# PIPTIK.net
KiCad netlist of a schematic drawn in Altium Designer
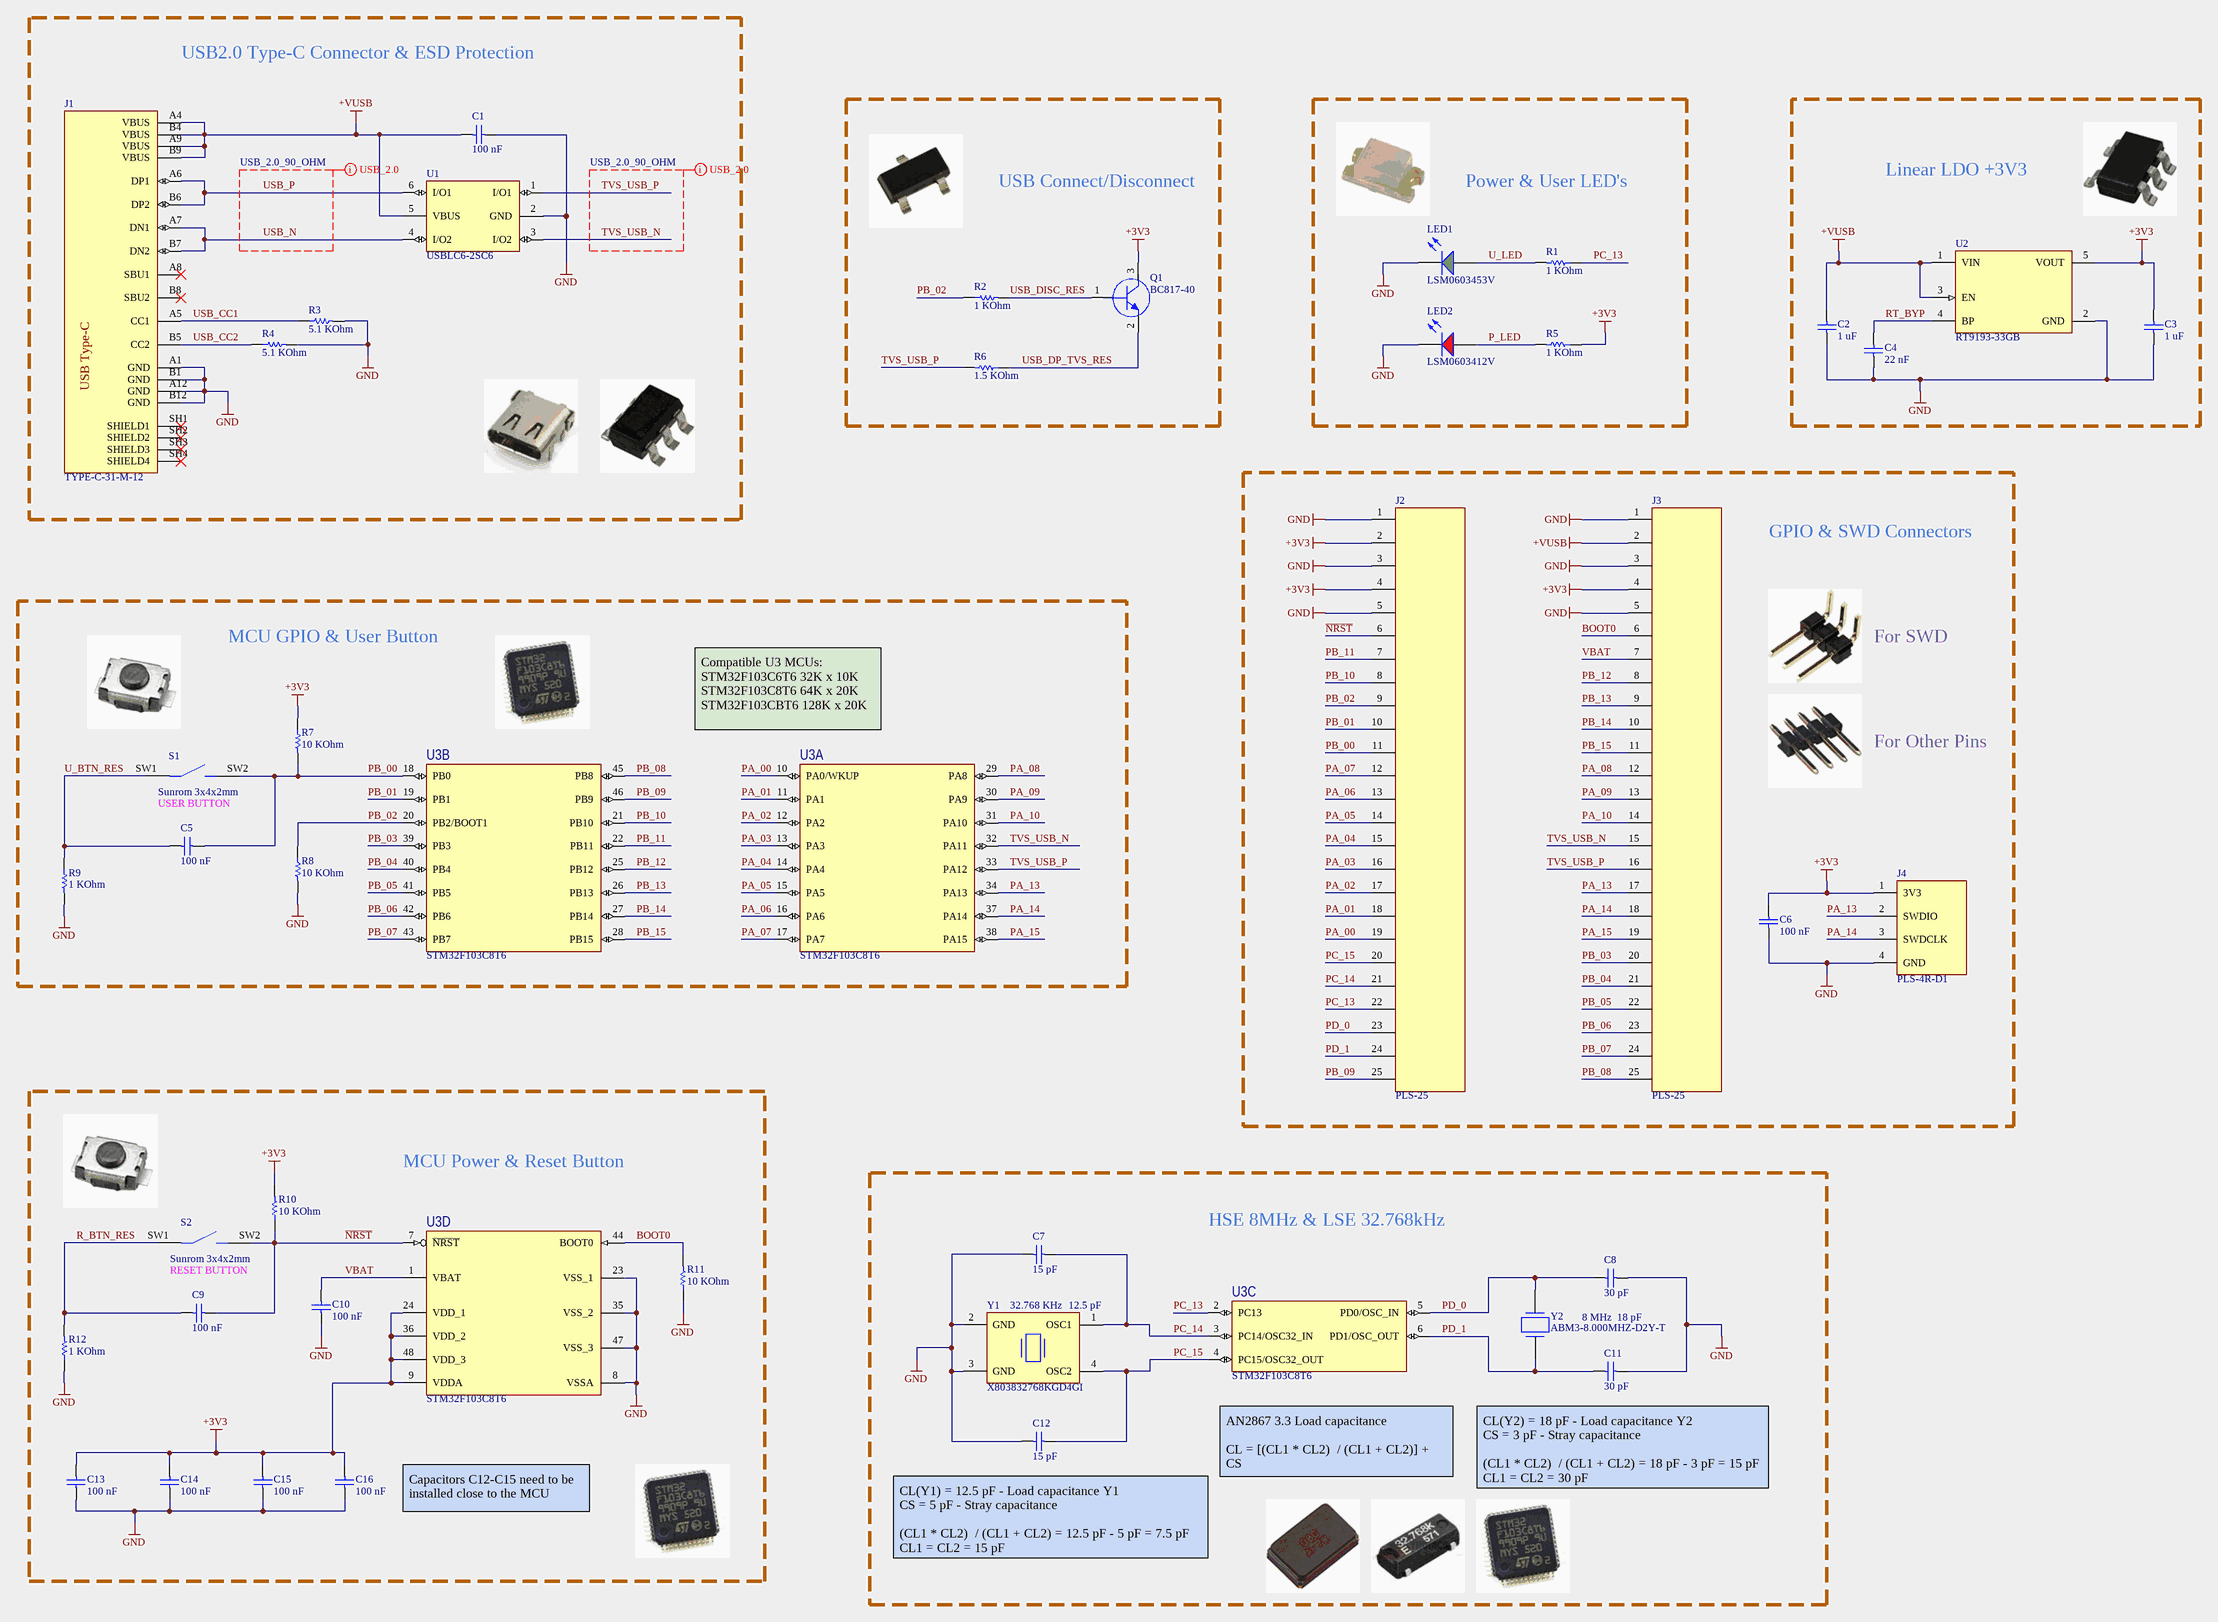
[diagram p0: PIPTIK.SchDoc]

(export (version "E")
  (design (tool "Eeschema 10.0.6"))
  (components
    (comp (ref "C1")
      (value "CAP-100N")
      (footprint "CAPC0603")
      (description "Chip Capacitor, 100 nF, +/- 5%")
      (fields (field (name "TOLERANCE") "5 %") (field (name "CAPACITANCE") "100 nF"))
      (libsource (lib "Конденсаторы керамические SMD") (part "CAP-100N"))
    )
    (comp (ref "C2")
      (value "CAP-1U")
      (footprint "CAPC0805")
      (description "Chip Capacitor, 1 uF, +/- 5%")
      (fields (field (name "TOLERANCE") "5 %") (field (name "CAPACITANCE") "1 uF"))
      (libsource (lib "Конденсаторы керамические SMD") (part "CAP-1U"))
    )
    (comp (ref "C3")
      (value "CAP-1U")
      (footprint "CAPC0805")
      (description "Chip Capacitor, 1 uF, +/- 5%")
      (fields (field (name "TOLERANCE") "5 %") (field (name "CAPACITANCE") "1 uF"))
      (libsource (lib "Конденсаторы керамические SMD") (part "CAP-1U"))
    )
    (comp (ref "C4")
      (value "CAP-22N")
      (footprint "CAPC0603")
      (description "Chip Capacitor, 22 nF, +/- 5%")
      (fields (field (name "TOLERANCE") "5 %") (field (name "CAPACITANCE") "22 nF"))
      (libsource (lib "Конденсаторы керамические SMD") (part "CAP-22N"))
    )
    (comp (ref "C5")
      (value "CAP-100N")
      (footprint "CAPC0603")
      (description "Chip Capacitor, 100 nF, +/- 5%")
      (fields (field (name "TOLERANCE") "5 %") (field (name "CAPACITANCE") "100 nF"))
      (libsource (lib "Конденсаторы керамические SMD") (part "CAP-100N"))
    )
    (comp (ref "C6")
      (value "CAP-100N")
      (footprint "CAPC0603")
      (description "Chip Capacitor, 100 nF, +/- 5%")
      (fields (field (name "TOLERANCE") "5 %") (field (name "CAPACITANCE") "100 nF"))
      (libsource (lib "Конденсаторы керамические SMD") (part "CAP-100N"))
    )
    (comp (ref "C7")
      (value "CAP-15P")
      (footprint "CAPC0603")
      (description "Chip Capacitor, 15 pF, +/- 5%")
      (fields (field (name "TOLERANCE") "5 %") (field (name "CAPACITANCE") "15 pF"))
      (libsource (lib "Конденсаторы керамические SMD") (part "CAP-15P"))
    )
    (comp (ref "C8")
      (value "CAP-30P")
      (footprint "CAPC0603")
      (description "Chip Capacitor, 30 pF, +/- 5%")
      (fields (field (name "TOLERANCE") "5 %") (field (name "CAPACITANCE") "30 pF"))
      (libsource (lib "Конденсаторы керамические SMD") (part "CAP-30P"))
    )
    (comp (ref "C9")
      (value "CAP-100N")
      (footprint "CAPC0603")
      (description "Chip Capacitor, 100 nF, +/- 5%")
      (fields (field (name "TOLERANCE") "5 %") (field (name "CAPACITANCE") "100 nF"))
      (libsource (lib "Конденсаторы керамические SMD") (part "CAP-100N"))
    )
    (comp (ref "C10")
      (value "CAP-100N")
      (footprint "CAPC0603")
      (description "Chip Capacitor, 100 nF, +/- 5%")
      (fields (field (name "TOLERANCE") "5 %") (field (name "CAPACITANCE") "100 nF"))
      (libsource (lib "Конденсаторы керамические SMD") (part "CAP-100N"))
    )
    (comp (ref "C11")
      (value "CAP-30P")
      (footprint "CAPC0603")
      (description "Chip Capacitor, 30 pF, +/- 5%")
      (fields (field (name "TOLERANCE") "5 %") (field (name "CAPACITANCE") "30 pF"))
      (libsource (lib "Конденсаторы керамические SMD") (part "CAP-30P"))
    )
    (comp (ref "C12")
      (value "CAP-15P")
      (footprint "CAPC0603")
      (description "Chip Capacitor, 15 pF, +/- 5%")
      (fields (field (name "TOLERANCE") "5 %") (field (name "CAPACITANCE") "15 pF"))
      (libsource (lib "Конденсаторы керамические SMD") (part "CAP-15P"))
    )
    (comp (ref "C13")
      (value "CAP-100N")
      (footprint "CAPC0603")
      (description "Chip Capacitor, 100 nF, +/- 5%")
      (fields (field (name "TOLERANCE") "5 %") (field (name "CAPACITANCE") "100 nF"))
      (libsource (lib "Конденсаторы керамические SMD") (part "CAP-100N"))
    )
    (comp (ref "C14")
      (value "CAP-100N")
      (footprint "CAPC0603")
      (description "Chip Capacitor, 100 nF, +/- 5%")
      (fields (field (name "TOLERANCE") "5 %") (field (name "CAPACITANCE") "100 nF"))
      (libsource (lib "Конденсаторы керамические SMD") (part "CAP-100N"))
    )
    (comp (ref "C15")
      (value "CAP-100N")
      (footprint "CAPC0603")
      (description "Chip Capacitor, 100 nF, +/- 5%")
      (fields (field (name "TOLERANCE") "5 %") (field (name "CAPACITANCE") "100 nF"))
      (libsource (lib "Конденсаторы керамические SMD") (part "CAP-100N"))
    )
    (comp (ref "C16")
      (value "CAP-100N")
      (footprint "CAPC0603")
      (description "Chip Capacitor, 100 nF, +/- 5%")
      (fields (field (name "TOLERANCE") "5 %") (field (name "CAPACITANCE") "100 nF"))
      (libsource (lib "Конденсаторы керамические SMD") (part "CAP-100N"))
    )
    (comp (ref "J1")
      (value "TYPE-C-31-M-12")
      (footprint "TYPE-C-31-M-12")
      (description "USB - Type C Female 16 8.94*7.3mm USB Connectors")
      (fields (field (name "PARTNUMBER") "TYPE-C-31-M-12"))
      (libsource (lib "Разъемы") (part "TYPE-C-31-M-12"))
    )
    (comp (ref "J2")
      (value "PLS-25")
      (footprint "PLS-25")
      (fields (field (name "PARTNUMBER") "PLS-25"))
      (libsource (lib "Разъемы") (part "PLS-25"))
    )
    (comp (ref "J3")
      (value "PLS-25")
      (footprint "PLS-25")
      (fields (field (name "PARTNUMBER") "PLS-25"))
      (libsource (lib "Разъемы") (part "PLS-25"))
    )
    (comp (ref "J4")
      (value "PLS-4RD")
      (footprint "PLS-4R-D1")
      (fields (field (name "PARTNUMBER") "PLS-4R-D1"))
      (libsource (lib "Разъемы") (part "PLS-4RD"))
    )
    (comp (ref "LED1")
      (value "LSM0603453V")
      (footprint "LSM0603-Series")
      (description "Green LED 0603 3V 20mA")
      (fields (field (name "PARTNUMBER") "LSM0603453V"))
      (libsource (lib "Светодиоды") (part "LSM0603453V"))
    )
    (comp (ref "LED2")
      (value "LSM0603412V")
      (footprint "LSM0603-Series")
      (description "Red LED 0603 2V 20mA")
      (fields (field (name "PARTNUMBER") "LSM0603412V"))
      (libsource (lib "Светодиоды") (part "LSM0603412V"))
    )
    (comp (ref "Q1")
      (value "BC817-40")
      (footprint "SOT23-3-AnBon")
      (description "NPN 500mA 45V 300mW SOT-23, hFE 250-600")
      (fields (field (name "PARTNUMBER") "BC817-40"))
      (libsource (lib "Транзисторы биполярные") (part "BC817-40"))
    )
    (comp (ref "R1")
      (value "RES-1K")
      (footprint "RES0603")
      (description "Chip Resistor, 1 KOhm, +/- 1%")
      (fields (field (name "TOLERANCE") "1 %") (field (name "RESISTANCE") "1 KOhm"))
      (libsource (lib "Резисторы SMD") (part "RES-1K"))
    )
    (comp (ref "R2")
      (value "RES-1K")
      (footprint "RES0603")
      (description "Chip Resistor, 1 KOhm, +/- 1%")
      (fields (field (name "TOLERANCE") "1 %") (field (name "RESISTANCE") "1 KOhm"))
      (libsource (lib "Резисторы SMD") (part "RES-1K"))
    )
    (comp (ref "R3")
      (value "RES-5K1")
      (footprint "RES0603")
      (description "Chip Resistor, 5.1 KOhm, +/- 1%")
      (fields (field (name "TOLERANCE") "1 %") (field (name "RESISTANCE") "5.1 KOhm"))
      (libsource (lib "Резисторы SMD") (part "RES-5K1"))
    )
    (comp (ref "R4")
      (value "RES-5K1")
      (footprint "RES0603")
      (description "Chip Resistor, 5.1 KOhm, +/- 1%")
      (fields (field (name "TOLERANCE") "1 %") (field (name "RESISTANCE") "5.1 KOhm"))
      (libsource (lib "Резисторы SMD") (part "RES-5K1"))
    )
    (comp (ref "R5")
      (value "RES-1K")
      (footprint "RES0603")
      (description "Chip Resistor, 1 KOhm, +/- 1%")
      (fields (field (name "TOLERANCE") "1 %") (field (name "RESISTANCE") "1 KOhm"))
      (libsource (lib "Резисторы SMD") (part "RES-1K"))
    )
    (comp (ref "R6")
      (value "RES-1K5")
      (footprint "RES0603")
      (description "Chip Resistor, 1.5 KOhm, +/- 1%")
      (fields (field (name "TOLERANCE") "1 %") (field (name "RESISTANCE") "1.5 KOhm"))
      (libsource (lib "Резисторы SMD") (part "RES-1K5"))
    )
    (comp (ref "R7")
      (value "RES-10K")
      (footprint "RES0603")
      (description "Chip Resistor, 10 KOhm, +/- 1%")
      (fields (field (name "TOLERANCE") "1 %") (field (name "RESISTANCE") "10 KOhm"))
      (libsource (lib "Резисторы SMD") (part "RES-10K"))
    )
    (comp (ref "R8")
      (value "RES-10K")
      (footprint "RES0603")
      (description "Chip Resistor, 10 KOhm, +/- 1%")
      (fields (field (name "TOLERANCE") "1 %") (field (name "RESISTANCE") "10 KOhm"))
      (libsource (lib "Резисторы SMD") (part "RES-10K"))
    )
    (comp (ref "R9")
      (value "RES-1K")
      (footprint "RES0603")
      (description "Chip Resistor, 1 KOhm, +/- 1%")
      (fields (field (name "TOLERANCE") "1 %") (field (name "RESISTANCE") "1 KOhm"))
      (libsource (lib "Резисторы SMD") (part "RES-1K"))
    )
    (comp (ref "R10")
      (value "RES-10K")
      (footprint "RES0603")
      (description "Chip Resistor, 10 KOhm, +/- 1%")
      (fields (field (name "TOLERANCE") "1 %") (field (name "RESISTANCE") "10 KOhm"))
      (libsource (lib "Резисторы SMD") (part "RES-10K"))
    )
    (comp (ref "R11")
      (value "RES-10K")
      (footprint "RES0603")
      (description "Chip Resistor, 10 KOhm, +/- 1%")
      (fields (field (name "TOLERANCE") "1 %") (field (name "RESISTANCE") "10 KOhm"))
      (libsource (lib "Резисторы SMD") (part "RES-10K"))
    )
    (comp (ref "R12")
      (value "RES-1K")
      (footprint "RES0603")
      (description "Chip Resistor, 1 KOhm, +/- 1%")
      (fields (field (name "TOLERANCE") "1 %") (field (name "RESISTANCE") "1 KOhm"))
      (libsource (lib "Резисторы SMD") (part "RES-1K"))
    )
    (comp (ref "S1")
      (value "USER BUTTON")
      (footprint "Tactile Switch SMD 3x4x2")
      (description "SMD Tactile Switch, sunrom 3x4x2mm 2-Pin 12V DC 0.2A")
      (fields (field (name "MODEL") "Sunrom 3x4x2mm"))
      (libsource (lib "Кнопки") (part "Tactile Switch 3x4x2mm"))
    )
    (comp (ref "S2")
      (value "RESET BUTTON")
      (footprint "Tactile Switch SMD 3x4x2")
      (description "SMD Tactile Switch, sunrom 3x4x2mm 2-Pin 12V DC 0.2A")
      (fields (field (name "MODEL") "Sunrom 3x4x2mm"))
      (libsource (lib "Кнопки") (part "Tactile Switch 3x4x2mm"))
    )
    (comp (ref "U1")
      (value "USBLC6-2SC6")
      (footprint "SOT23-6L-STM")
      (description "Very low capacitance ESD protection  3.5 pF max")
      (fields (field (name "PARTNUMBER") "USBLC6-2SC6"))
      (libsource (lib "Диоды TVS") (part "USBLC6-2SC6"))
    )
    (comp (ref "U2")
      (value "RT9193-33GB")
      (footprint "SOT-23-5-RICHTEK")
      (description "Fixed 5.5V 3.3V 220mV @ 300mA SOT-23-5 Dropout Regulators(LDO)")
      (fields (field (name "PARTNUMBER") "RT9193-33GB"))
      (libsource (lib "Регуляотры напряжения") (part "RT9193-33GB"))
    )
    (comp (ref "U3")
      (value "STM32F103C8T6")
      (footprint "LQFP-48-STM32")
      (description "ARM based 32-bit MCU with 64 or 128 KB Flash")
      (fields (field (name "PARTNUMBER") "STM32F103C8T6"))
      (libsource (lib "Микроконтроллеры") (part "STM32F103C8T6"))
    )
    (comp (ref "Y1")
      (value "X803832768KGD4GI")
      (footprint "YSX-306G-A")
      (description "32.768KHz ±20ppm 12.5pF 50kΩ MC-306 SMD Crystal Resonators")
      (fields
        (field (name "FREQUENCY") "32.768 KHz")
        (field (name "PARTNUMBER") "X803832768KGD4GI")
        (field (name "LOADCAPACITANCE") "12.5 pF")
      )
      (libsource (lib "Кврцы") (part "X803832768KGD4GI"))
    )
    (comp (ref "Y2")
      (value "ABM3-8.000MHZ-D2Y-T")
      (footprint "ABM3-2P")
      (description "8MHz ±20ppm 18pF 140 Ohm SMD Crystal Resonators")
      (fields
        (field (name "FREQUENCY") "8 MHz")
        (field (name "PARTNUMBER") "ABM3-8.000MHZ-D2Y-T")
        (field (name "LOADCAPACITANCE") "18 pF")
      )
      (libsource (lib "Кврцы") (part "ABM3-8.000MHZ-D2Y-T"))
    )
  )
  (nets
    (net (code "1") (name "+3V3") (class "Default")
      (node (ref "C13") (pin "2") (pinfunction "2_2") (pintype "passive"))
      (node (ref "C14") (pin "2") (pinfunction "2_2") (pintype "passive"))
      (node (ref "C15") (pin "2") (pinfunction "2_2") (pintype "passive"))
      (node (ref "C16") (pin "2") (pinfunction "2_2") (pintype "passive"))
      (node (ref "C3") (pin "2") (pinfunction "2_2") (pintype "passive"))
      (node (ref "C6") (pin "1") (pinfunction "1_1") (pintype "passive"))
      (node (ref "J2") (pin "2") (pinfunction "*_2") (pintype "passive"))
      (node (ref "J2") (pin "4") (pinfunction "*_4") (pintype "passive"))
      (node (ref "J3") (pin "4") (pinfunction "*_4") (pintype "passive"))
      (node (ref "J4") (pin "1") (pinfunction "3V3_1") (pintype "passive"))
      (node (ref "Q1") (pin "3") (pinfunction "C_3") (pintype "passive"))
      (node (ref "R10") (pin "2") (pinfunction "2_2") (pintype "passive"))
      (node (ref "R5") (pin "1") (pinfunction "1_1") (pintype "passive"))
      (node (ref "R7") (pin "1") (pinfunction "1_1") (pintype "passive"))
      (node (ref "U2") (pin "5") (pinfunction "VOUT_5") (pintype "power_in"))
      (node (ref "U3") (pin "24") (pinfunction "VDD_1_24") (pintype "power_in"))
      (node (ref "U3") (pin "36") (pinfunction "VDD_2_36") (pintype "power_in"))
      (node (ref "U3") (pin "48") (pinfunction "VDD_3_48") (pintype "power_in"))
      (node (ref "U3") (pin "9") (pinfunction "VDDA_9") (pintype "power_in"))
    )
    (net (code "2") (name "+VUSB") (class "Default")
      (node (ref "C1") (pin "2") (pinfunction "2_2") (pintype "passive"))
      (node (ref "C2") (pin "2") (pinfunction "2_2") (pintype "passive"))
      (node (ref "J1") (pin "A4") (pinfunction "VBUS_A4") (pintype "power_in"))
      (node (ref "J1") (pin "A9") (pinfunction "VBUS_A9") (pintype "power_in"))
      (node (ref "J1") (pin "B4") (pinfunction "VBUS_B4") (pintype "power_in"))
      (node (ref "J1") (pin "B9") (pinfunction "VBUS_B9") (pintype "power_in"))
      (node (ref "J3") (pin "2") (pinfunction "*_2") (pintype "passive"))
      (node (ref "U1") (pin "5") (pinfunction "VBUS_5") (pintype "power_in"))
      (node (ref "U2") (pin "1") (pinfunction "VIN_1") (pintype "power_in"))
      (node (ref "U2") (pin "3") (pinfunction "EN_3") (pintype "input"))
    )
    (net (code "3") (name "/BOOT0") (class "Default")
      (node (ref "J3") (pin "6") (pinfunction "*_6") (pintype "passive"))
      (node (ref "R11") (pin "2") (pinfunction "2_2") (pintype "passive"))
      (node (ref "U3") (pin "44") (pinfunction "BOOT0_44") (pintype "input"))
    )
    (net (code "4") (name "/PA_00") (class "Default")
      (node (ref "J2") (pin "19") (pinfunction "*_19") (pintype "passive"))
      (node (ref "U3") (pin "10") (pinfunction "PA0/WKUP_10") (pintype "bidirectional"))
    )
    (net (code "5") (name "/PA_01") (class "Default")
      (node (ref "J2") (pin "18") (pinfunction "*_18") (pintype "passive"))
      (node (ref "U3") (pin "11") (pinfunction "PA1_11") (pintype "bidirectional"))
    )
    (net (code "6") (name "/PA_02") (class "Default")
      (node (ref "J2") (pin "17") (pinfunction "*_17") (pintype "passive"))
      (node (ref "U3") (pin "12") (pinfunction "PA2_12") (pintype "bidirectional"))
    )
    (net (code "7") (name "/PA_03") (class "Default")
      (node (ref "J2") (pin "16") (pinfunction "*_16") (pintype "passive"))
      (node (ref "U3") (pin "13") (pinfunction "PA3_13") (pintype "bidirectional"))
    )
    (net (code "8") (name "/PA_04") (class "Default")
      (node (ref "J2") (pin "15") (pinfunction "*_15") (pintype "passive"))
      (node (ref "U3") (pin "14") (pinfunction "PA4_14") (pintype "bidirectional"))
    )
    (net (code "9") (name "/PA_05") (class "Default")
      (node (ref "J2") (pin "14") (pinfunction "*_14") (pintype "passive"))
      (node (ref "U3") (pin "15") (pinfunction "PA5_15") (pintype "bidirectional"))
    )
    (net (code "10") (name "/PA_06") (class "Default")
      (node (ref "J2") (pin "13") (pinfunction "*_13") (pintype "passive"))
      (node (ref "U3") (pin "16") (pinfunction "PA6_16") (pintype "bidirectional"))
    )
    (net (code "11") (name "/PA_07") (class "Default")
      (node (ref "J2") (pin "12") (pinfunction "*_12") (pintype "passive"))
      (node (ref "U3") (pin "17") (pinfunction "PA7_17") (pintype "bidirectional"))
    )
    (net (code "12") (name "/PA_08") (class "Default")
      (node (ref "J3") (pin "12") (pinfunction "*_12") (pintype "passive"))
      (node (ref "U3") (pin "29") (pinfunction "PA8_29") (pintype "bidirectional"))
    )
    (net (code "13") (name "/PA_09") (class "Default")
      (node (ref "J3") (pin "13") (pinfunction "*_13") (pintype "passive"))
      (node (ref "U3") (pin "30") (pinfunction "PA9_30") (pintype "bidirectional"))
    )
    (net (code "14") (name "/PA_10") (class "Default")
      (node (ref "J3") (pin "14") (pinfunction "*_14") (pintype "passive"))
      (node (ref "U3") (pin "31") (pinfunction "PA10_31") (pintype "bidirectional"))
    )
    (net (code "15") (name "/PA_13") (class "Default")
      (node (ref "J3") (pin "17") (pinfunction "*_17") (pintype "passive"))
      (node (ref "J4") (pin "2") (pinfunction "SWDIO_2") (pintype "passive"))
      (node (ref "U3") (pin "34") (pinfunction "PA13_34") (pintype "bidirectional"))
    )
    (net (code "16") (name "/PA_14") (class "Default")
      (node (ref "J3") (pin "18") (pinfunction "*_18") (pintype "passive"))
      (node (ref "J4") (pin "3") (pinfunction "SWDCLK_3") (pintype "passive"))
      (node (ref "U3") (pin "37") (pinfunction "PA14_37") (pintype "bidirectional"))
    )
    (net (code "17") (name "/PA_15") (class "Default")
      (node (ref "J3") (pin "19") (pinfunction "*_19") (pintype "passive"))
      (node (ref "U3") (pin "38") (pinfunction "PA15_38") (pintype "bidirectional"))
    )
    (net (code "18") (name "/PB_00") (class "Default")
      (node (ref "C5") (pin "1") (pinfunction "1_1") (pintype "passive"))
      (node (ref "J2") (pin "11") (pinfunction "*_11") (pintype "passive"))
      (node (ref "R7") (pin "2") (pinfunction "2_2") (pintype "passive"))
      (node (ref "S1") (pin "SW2") (pintype "passive"))
      (node (ref "U3") (pin "18") (pinfunction "PB0_18") (pintype "bidirectional"))
    )
    (net (code "19") (name "/PB_01") (class "Default")
      (node (ref "J2") (pin "10") (pinfunction "*_10") (pintype "passive"))
      (node (ref "U3") (pin "19") (pinfunction "PB1_19") (pintype "bidirectional"))
    )
    (net (code "20") (name "/PB_02") (class "Default")
      (node (ref "J2") (pin "9") (pinfunction "*_9") (pintype "passive"))
      (node (ref "R2") (pin "1") (pinfunction "1_1") (pintype "passive"))
      (node (ref "R8") (pin "1") (pinfunction "1_1") (pintype "passive"))
      (node (ref "U3") (pin "20") (pinfunction "PB2/BOOT1_20") (pintype "bidirectional"))
    )
    (net (code "21") (name "/PB_03") (class "Default")
      (node (ref "J3") (pin "20") (pinfunction "*_20") (pintype "passive"))
      (node (ref "U3") (pin "39") (pinfunction "PB3_39") (pintype "bidirectional"))
    )
    (net (code "22") (name "/PB_04") (class "Default")
      (node (ref "J3") (pin "21") (pinfunction "*_21") (pintype "passive"))
      (node (ref "U3") (pin "40") (pinfunction "PB4_40") (pintype "bidirectional"))
    )
    (net (code "23") (name "/PB_05") (class "Default")
      (node (ref "J3") (pin "22") (pinfunction "*_22") (pintype "passive"))
      (node (ref "U3") (pin "41") (pinfunction "PB5_41") (pintype "bidirectional"))
    )
    (net (code "24") (name "/PB_06") (class "Default")
      (node (ref "J3") (pin "23") (pinfunction "*_23") (pintype "passive"))
      (node (ref "U3") (pin "42") (pinfunction "PB6_42") (pintype "bidirectional"))
    )
    (net (code "25") (name "/PB_07") (class "Default")
      (node (ref "J3") (pin "24") (pinfunction "*_24") (pintype "passive"))
      (node (ref "U3") (pin "43") (pinfunction "PB7_43") (pintype "bidirectional"))
    )
    (net (code "26") (name "/PB_08") (class "Default")
      (node (ref "J3") (pin "25") (pinfunction "*_25") (pintype "passive"))
      (node (ref "U3") (pin "45") (pinfunction "PB8_45") (pintype "bidirectional"))
    )
    (net (code "27") (name "/PB_09") (class "Default")
      (node (ref "J2") (pin "25") (pinfunction "*_25") (pintype "passive"))
      (node (ref "U3") (pin "46") (pinfunction "PB9_46") (pintype "bidirectional"))
    )
    (net (code "28") (name "/PB_10") (class "Default")
      (node (ref "J2") (pin "8") (pinfunction "*_8") (pintype "passive"))
      (node (ref "U3") (pin "21") (pinfunction "PB10_21") (pintype "bidirectional"))
    )
    (net (code "29") (name "/PB_11") (class "Default")
      (node (ref "J2") (pin "7") (pinfunction "*_7") (pintype "passive"))
      (node (ref "U3") (pin "22") (pinfunction "PB11_22") (pintype "bidirectional"))
    )
    (net (code "30") (name "/PB_12") (class "Default")
      (node (ref "J3") (pin "8") (pinfunction "*_8") (pintype "passive"))
      (node (ref "U3") (pin "25") (pinfunction "PB12_25") (pintype "bidirectional"))
    )
    (net (code "31") (name "/PB_13") (class "Default")
      (node (ref "J3") (pin "9") (pinfunction "*_9") (pintype "passive"))
      (node (ref "U3") (pin "26") (pinfunction "PB13_26") (pintype "bidirectional"))
    )
    (net (code "32") (name "/PB_14") (class "Default")
      (node (ref "J3") (pin "10") (pinfunction "*_10") (pintype "passive"))
      (node (ref "U3") (pin "27") (pinfunction "PB14_27") (pintype "bidirectional"))
    )
    (net (code "33") (name "/PB_15") (class "Default")
      (node (ref "J3") (pin "11") (pinfunction "*_11") (pintype "passive"))
      (node (ref "U3") (pin "28") (pinfunction "PB15_28") (pintype "bidirectional"))
    )
    (net (code "34") (name "/PC_13") (class "Default")
      (node (ref "J2") (pin "22") (pinfunction "*_22") (pintype "passive"))
      (node (ref "R1") (pin "1") (pinfunction "1_1") (pintype "passive"))
      (node (ref "U3") (pin "2") (pinfunction "PC13/TAMPER-RTC_2") (pintype "bidirectional"))
    )
    (net (code "35") (name "/PC_14") (class "Default")
      (node (ref "C7") (pin "2") (pinfunction "2_2") (pintype "passive"))
      (node (ref "J2") (pin "21") (pinfunction "*_21") (pintype "passive"))
      (node (ref "U3") (pin "3") (pinfunction "PC14/OSC32_IN_3") (pintype "bidirectional"))
      (node (ref "Y1") (pin "1") (pinfunction "OSC1_1") (pintype "passive"))
    )
    (net (code "36") (name "/PC_15") (class "Default")
      (node (ref "C12") (pin "2") (pinfunction "2_2") (pintype "passive"))
      (node (ref "J2") (pin "20") (pinfunction "*_20") (pintype "passive"))
      (node (ref "U3") (pin "4") (pinfunction "PC15/OSC32_OUT_4") (pintype "bidirectional"))
      (node (ref "Y1") (pin "4") (pinfunction "OSC2_4") (pintype "passive"))
    )
    (net (code "37") (name "/PD_0") (class "Default")
      (node (ref "C8") (pin "1") (pinfunction "1_1") (pintype "passive"))
      (node (ref "J2") (pin "23") (pinfunction "*_23") (pintype "passive"))
      (node (ref "U3") (pin "5") (pinfunction "PD0/OSC_IN_5") (pintype "bidirectional"))
      (node (ref "Y2") (pin "2") (pinfunction "OSC2_2") (pintype "passive"))
    )
    (net (code "38") (name "/PD_1") (class "Default")
      (node (ref "C11") (pin "1") (pinfunction "1_1") (pintype "passive"))
      (node (ref "J2") (pin "24") (pinfunction "*_24") (pintype "passive"))
      (node (ref "U3") (pin "6") (pinfunction "PD1/OSC_OUT_6") (pintype "bidirectional"))
      (node (ref "Y2") (pin "1") (pinfunction "OSC1_1") (pintype "passive"))
    )
    (net (code "39") (name "/P_LED") (class "Default")
      (node (ref "LED2") (pin "2") (pinfunction "A_2") (pintype "passive"))
      (node (ref "R5") (pin "2") (pinfunction "2_2") (pintype "passive"))
    )
    (net (code "40") (name "/RT_BYP") (class "Default")
      (node (ref "C4") (pin "2") (pinfunction "2_2") (pintype "passive"))
      (node (ref "U2") (pin "4") (pinfunction "BP_4") (pintype "passive"))
    )
    (net (code "41") (name "/R_BTN_RES") (class "Default")
      (node (ref "C9") (pin "2") (pinfunction "2_2") (pintype "passive"))
      (node (ref "R12") (pin "2") (pinfunction "2_2") (pintype "passive"))
      (node (ref "S2") (pin "SW1") (pintype "passive"))
    )
    (net (code "42") (name "/TVS_USB_N") (class "Default")
      (node (ref "J3") (pin "15") (pinfunction "*_15") (pintype "passive"))
      (node (ref "U1") (pin "3") (pinfunction "I/O2_3") (pintype "bidirectional"))
      (node (ref "U3") (pin "32") (pinfunction "PA11_32") (pintype "bidirectional"))
    )
    (net (code "43") (name "/TVS_USB_P") (class "Default")
      (node (ref "J3") (pin "16") (pinfunction "*_16") (pintype "passive"))
      (node (ref "R6") (pin "2") (pinfunction "2_2") (pintype "passive"))
      (node (ref "U1") (pin "1") (pinfunction "I/O1_1") (pintype "bidirectional"))
      (node (ref "U3") (pin "33") (pinfunction "PA12_33") (pintype "bidirectional"))
    )
    (net (code "44") (name "/USB_CC1") (class "Default")
      (node (ref "J1") (pin "A5") (pinfunction "CC1_A5") (pintype "passive"))
      (node (ref "R3") (pin "1") (pinfunction "1_1") (pintype "passive"))
    )
    (net (code "45") (name "/USB_CC2") (class "Default")
      (node (ref "J1") (pin "B5") (pinfunction "CC2_B5") (pintype "passive"))
      (node (ref "R4") (pin "1") (pinfunction "1_1") (pintype "passive"))
    )
    (net (code "46") (name "/USB_DISC_RES") (class "Default")
      (node (ref "Q1") (pin "1") (pinfunction "B_1") (pintype "passive"))
      (node (ref "R2") (pin "2") (pinfunction "2_2") (pintype "passive"))
    )
    (net (code "47") (name "/USB_DP_TVS_RES") (class "Default")
      (node (ref "Q1") (pin "2") (pinfunction "E_2") (pintype "passive"))
      (node (ref "R6") (pin "1") (pinfunction "1_1") (pintype "passive"))
    )
    (net (code "48") (name "/USB_N") (class "Default")
      (node (ref "J1") (pin "A7") (pinfunction "DN1_A7") (pintype "bidirectional"))
      (node (ref "J1") (pin "B7") (pinfunction "DN2_B7") (pintype "bidirectional"))
      (node (ref "U1") (pin "4") (pinfunction "I/O2_4") (pintype "bidirectional"))
    )
    (net (code "49") (name "/USB_P") (class "Default")
      (node (ref "J1") (pin "A6") (pinfunction "DP1_A6") (pintype "bidirectional"))
      (node (ref "J1") (pin "B6") (pinfunction "DP2_B6") (pintype "bidirectional"))
      (node (ref "U1") (pin "6") (pinfunction "I/O1_6") (pintype "bidirectional"))
    )
    (net (code "50") (name "/U_BTN_RES") (class "Default")
      (node (ref "C5") (pin "2") (pinfunction "2_2") (pintype "passive"))
      (node (ref "R9") (pin "1") (pinfunction "1_1") (pintype "passive"))
      (node (ref "S1") (pin "SW1") (pintype "passive"))
    )
    (net (code "51") (name "/U_LED") (class "Default")
      (node (ref "LED1") (pin "2") (pinfunction "A_2") (pintype "passive"))
      (node (ref "R1") (pin "2") (pinfunction "2_2") (pintype "passive"))
    )
    (net (code "52") (name "/VBAT") (class "Default")
      (node (ref "C10") (pin "2") (pinfunction "2_2") (pintype "passive"))
      (node (ref "J3") (pin "7") (pinfunction "*_7") (pintype "passive"))
      (node (ref "U3") (pin "1") (pinfunction "VBAT_1") (pintype "power_in"))
    )
    (net (code "53") (name "/~{NRST}") (class "Default")
      (node (ref "C9") (pin "1") (pinfunction "1_1") (pintype "passive"))
      (node (ref "J2") (pin "6") (pinfunction "*_6") (pintype "passive"))
      (node (ref "R10") (pin "1") (pinfunction "1_1") (pintype "passive"))
      (node (ref "S2") (pin "SW2") (pintype "passive"))
      (node (ref "U3") (pin "7") (pinfunction "~{NRST}_7") (pintype "input"))
    )
    (net (code "54") (name "GND") (class "Default")
      (node (ref "C1") (pin "1") (pinfunction "1_1") (pintype "passive"))
      (node (ref "C10") (pin "1") (pinfunction "1_1") (pintype "passive"))
      (node (ref "C11") (pin "2") (pinfunction "2_2") (pintype "passive"))
      (node (ref "C12") (pin "1") (pinfunction "1_1") (pintype "passive"))
      (node (ref "C13") (pin "1") (pinfunction "1_1") (pintype "passive"))
      (node (ref "C14") (pin "1") (pinfunction "1_1") (pintype "passive"))
      (node (ref "C15") (pin "1") (pinfunction "1_1") (pintype "passive"))
      (node (ref "C16") (pin "1") (pinfunction "1_1") (pintype "passive"))
      (node (ref "C2") (pin "1") (pinfunction "1_1") (pintype "passive"))
      (node (ref "C3") (pin "1") (pinfunction "1_1") (pintype "passive"))
      (node (ref "C4") (pin "1") (pinfunction "1_1") (pintype "passive"))
      (node (ref "C6") (pin "2") (pinfunction "2_2") (pintype "passive"))
      (node (ref "C7") (pin "1") (pinfunction "1_1") (pintype "passive"))
      (node (ref "C8") (pin "2") (pinfunction "2_2") (pintype "passive"))
      (node (ref "J1") (pin "A1") (pinfunction "GND_A1") (pintype "power_in"))
      (node (ref "J1") (pin "A12") (pinfunction "GND_A12") (pintype "power_in"))
      (node (ref "J1") (pin "B1") (pinfunction "GND_B1") (pintype "power_in"))
      (node (ref "J1") (pin "B12") (pinfunction "GND_B12") (pintype "power_in"))
      (node (ref "J2") (pin "1") (pinfunction "*_1") (pintype "passive"))
      (node (ref "J2") (pin "3") (pinfunction "*_3") (pintype "passive"))
      (node (ref "J2") (pin "5") (pinfunction "*_5") (pintype "passive"))
      (node (ref "J3") (pin "1") (pinfunction "*_1") (pintype "passive"))
      (node (ref "J3") (pin "3") (pinfunction "*_3") (pintype "passive"))
      (node (ref "J3") (pin "5") (pinfunction "*_5") (pintype "passive"))
      (node (ref "J4") (pin "4") (pinfunction "GND_4") (pintype "passive"))
      (node (ref "LED1") (pin "1") (pinfunction "K_1") (pintype "passive"))
      (node (ref "LED2") (pin "1") (pinfunction "K_1") (pintype "passive"))
      (node (ref "R11") (pin "1") (pinfunction "1_1") (pintype "passive"))
      (node (ref "R12") (pin "1") (pinfunction "1_1") (pintype "passive"))
      (node (ref "R3") (pin "2") (pinfunction "2_2") (pintype "passive"))
      (node (ref "R4") (pin "2") (pinfunction "2_2") (pintype "passive"))
      (node (ref "R8") (pin "2") (pinfunction "2_2") (pintype "passive"))
      (node (ref "R9") (pin "2") (pinfunction "2_2") (pintype "passive"))
      (node (ref "U1") (pin "2") (pinfunction "GND_2") (pintype "power_in"))
      (node (ref "U2") (pin "2") (pinfunction "GND_2") (pintype "power_in"))
      (node (ref "U3") (pin "23") (pinfunction "VSS_1_23") (pintype "power_in"))
      (node (ref "U3") (pin "35") (pinfunction "VSS_2_35") (pintype "power_in"))
      (node (ref "U3") (pin "47") (pinfunction "VSS_3_47") (pintype "power_in"))
      (node (ref "U3") (pin "8") (pinfunction "VSSA_8") (pintype "power_in"))
      (node (ref "Y1") (pin "2") (pinfunction "GND_2") (pintype "passive"))
      (node (ref "Y1") (pin "3") (pinfunction "GND_3") (pintype "passive"))
    )
    (net (code "55") (name "unconnected-(J1-SBU1-PadA8)") (class "Default")
      (node (ref "J1") (pin "A8") (pinfunction "SBU1_A8") (pintype "passive+no_connect"))
    )
    (net (code "56") (name "unconnected-(J1-SBU2-PadB8)") (class "Default")
      (node (ref "J1") (pin "B8") (pinfunction "SBU2_B8") (pintype "passive+no_connect"))
    )
    (net (code "57") (name "unconnected-(J1-SHIELD1-PadSH1)") (class "Default")
      (node (ref "J1") (pin "SH1") (pinfunction "SHIELD1_SH1") (pintype "power_in+no_connect"))
    )
    (net (code "58") (name "unconnected-(J1-SHIELD2-PadSH2)") (class "Default")
      (node (ref "J1") (pin "SH2") (pinfunction "SHIELD2_SH2") (pintype "power_in+no_connect"))
    )
    (net (code "59") (name "unconnected-(J1-SHIELD3-PadSH3)") (class "Default")
      (node (ref "J1") (pin "SH3") (pinfunction "SHIELD3_SH3") (pintype "power_in+no_connect"))
    )
    (net (code "60") (name "unconnected-(J1-SHIELD4-PadSH4)") (class "Default")
      (node (ref "J1") (pin "SH4") (pinfunction "SHIELD4_SH4") (pintype "power_in+no_connect"))
    )
  )
)
